# Pedal_SCH.net
KiCad netlist of a schematic drawn in Altium Designer
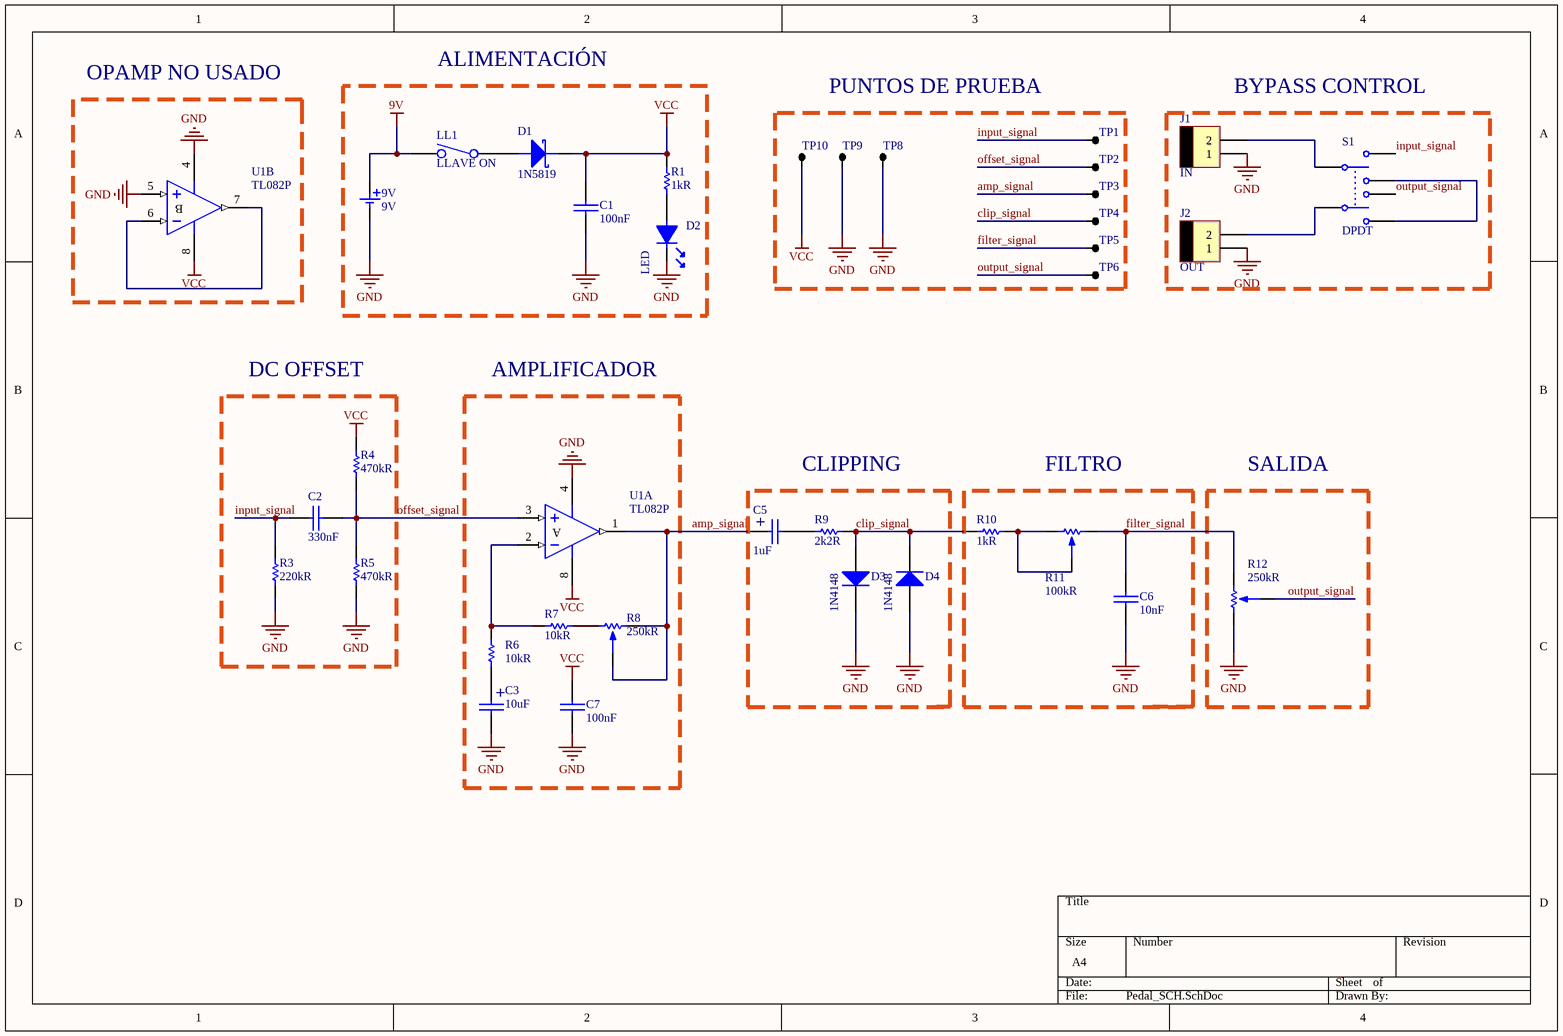
[diagram p0: Pedal_SCH.SchDoc]

(export (version "E")
  (design (tool "Eeschema 10.0.6"))
  (components
    (comp (ref "9V")
      (value "9V")
      (footprint "MOLEX2")
      (description "BATERIA")
      (libsource (lib "LIBEBAL") (part "BATERIA"))
    )
    (comp (ref "C1") (value "100nF") (footprint "0805") (libsource (lib "LIBEBAL") (part "CAP")))
    (comp (ref "C2") (value "330nF") (footprint "CAP_FILM") (libsource (lib "LIBEBAL") (part "CAP")))
    (comp (ref "C3") (value "10uF") (footprint "CAP100RP") (libsource (lib "LIBEBAL") (part "CAPPOL")))
    (comp (ref "C5") (value "1uF") (footprint "CAP100RP") (libsource (lib "LIBEBAL") (part "CAPPOL")))
    (comp (ref "C6") (value "10nF") (footprint "CAP_FILM_POLY") (libsource (lib "LIBEBAL") (part "CAP")))
    (comp (ref "C7") (value "100nF") (footprint "0805") (libsource (lib "LIBEBAL") (part "CAP")))
    (comp (ref "D1") (value "1N5819") (footprint "DO-41") (libsource (lib "LIB2013") (part "DIODE SCHOTTKY")))
    (comp (ref "D2") (value "LED") (footprint "MOLEX2") (libsource (lib "LIBEBAL") (part "LED")))
    (comp (ref "D3")
      (value "1N4148")
      (footprint "DO-35")
      (description "High Conductance Fast Diode")
      (libsource (lib "Miscellaneous Devices") (part "Diode 1N4148"))
    )
    (comp (ref "D4")
      (value "1N4148")
      (footprint "DO-35")
      (description "High Conductance Fast Diode")
      (libsource (lib "Miscellaneous Devices") (part "Diode 1N4148"))
    )
    (comp (ref "J1")
      (value "IN")
      (footprint "MOLEX2")
      (description "INPUT")
      (libsource (lib "LIBEBAL") (part "MOLEX2"))
    )
    (comp (ref "J2") (value "OUT") (footprint "MOLEX2") (libsource (lib "LIBEBAL") (part "MOLEX2")))
    (comp (ref "LL1")
      (value "LLAVE ON")
      (footprint "MOLEX2")
      (description "Llave ON")
      (libsource (lib "LIB2013") (part "LLAVE ON"))
    )
    (comp (ref "R1") (value "1kR") (footprint "0805") (libsource (lib "LIBEBAL") (part "RES")))
    (comp (ref "R3") (value "220kR") (footprint "0805") (libsource (lib "LIBEBAL") (part "RES")))
    (comp (ref "R4") (value "470kR") (footprint "0805") (libsource (lib "LIBEBAL") (part "RES")))
    (comp (ref "R5") (value "470kR") (footprint "0805") (libsource (lib "LIBEBAL") (part "RES")))
    (comp (ref "R6") (value "10kR") (footprint "0805") (libsource (lib "LIBEBAL") (part "RES")))
    (comp (ref "R7") (value "10kR") (footprint "0805") (libsource (lib "LIBEBAL") (part "RES")))
    (comp (ref "R8") (value "250kR") (footprint "MOLEX3") (libsource (lib "") (part "POTENCIOMETRO_1")))
    (comp (ref "R9") (value "2k2R") (footprint "0805") (libsource (lib "LIBEBAL") (part "RES")))
    (comp (ref "R10") (value "1kR") (footprint "0805") (libsource (lib "LIBEBAL") (part "RES")))
    (comp (ref "R11") (value "100kR") (footprint "MOLEX3") (libsource (lib "") (part "POTENCIOMETRO_1")))
    (comp (ref "R12") (value "250kR") (footprint "MOLEX3") (libsource (lib "LIBEBAL") (part "POTENCIOMETRO")))
    (comp (ref "S1")
      (value "DPDT")
      (footprint "MOLEX6")
      (description "Double-Pole, Double-Throw Switch")
      (fields (field (name "PUBLISHER") "Altium Limited"))
      (libsource (lib "Miscellaneous Devices") (part "SW-DPDT"))
    )
    (comp (ref "TP1") (value "IN") (footprint "TPTH") (libsource (lib "LIBEBAL") (part "TP")))
    (comp (ref "TP2") (value "OFF") (footprint "TPTH") (libsource (lib "LIBEBAL") (part "TP")))
    (comp (ref "TP3") (value "AMP") (footprint "TPTH") (libsource (lib "LIBEBAL") (part "TP")))
    (comp (ref "TP4") (value "CLI") (footprint "TPTH") (libsource (lib "LIBEBAL") (part "TP")))
    (comp (ref "TP5") (value "FIL") (footprint "TPTH") (libsource (lib "LIBEBAL") (part "TP")))
    (comp (ref "TP6") (value "OUT") (footprint "TPTH") (libsource (lib "LIBEBAL") (part "TP")))
    (comp (ref "TP8") (value "GND") (footprint "TPTH") (libsource (lib "LIBEBAL") (part "TP")))
    (comp (ref "TP9") (value "GND") (footprint "TPTH") (libsource (lib "LIBEBAL") (part "TP")))
    (comp (ref "TP10") (value "VCC") (footprint "TPTH") (libsource (lib "LIBEBAL") (part "TP")))
    (comp (ref "U1")
      (value "TL082P")
      (footprint "Pedal_PCB:P008")
      (description "JFET-Input Operational Amplifier")
      (fields (field (name "PUBLISHER") "Altium Limited"))
      (libsource (lib "Pedal_SCH") (part "TL082P"))
    )
  )
  (nets
    (net (code "1") (name "/amp_signal") (class "Default")
      (node (ref "C5") (pin "1") (pinfunction "1_1") (pintype "passive"))
      (node (ref "R8") (pin "1") (pinfunction "1_1") (pintype "passive"))
      (node (ref "R8") (pin "2") (pinfunction "2_2") (pintype "passive"))
      (node (ref "TP3") (pin "1") (pinfunction "1_1") (pintype "passive"))
      (node (ref "U1") (pin "1") (pinfunction "OUT_1") (pintype "output"))
    )
    (net (code "2") (name "/clip_signal") (class "Default")
      (node (ref "D3") (pin "1") (pinfunction "A_1") (pintype "passive"))
      (node (ref "D4") (pin "2") (pinfunction "K_2") (pintype "passive"))
      (node (ref "R10") (pin "2") (pinfunction "2_2") (pintype "passive"))
      (node (ref "R9") (pin "2") (pinfunction "2_2") (pintype "passive"))
      (node (ref "TP4") (pin "1") (pinfunction "1_1") (pintype "passive"))
    )
    (net (code "3") (name "/filter_signal") (class "Default")
      (node (ref "C6") (pin "1") (pinfunction "1_1") (pintype "passive"))
      (node (ref "R11") (pin "1") (pinfunction "1_1") (pintype "passive"))
      (node (ref "R12") (pin "1") (pinfunction "1_1") (pintype "passive"))
      (node (ref "TP5") (pin "1") (pinfunction "1_1") (pintype "passive"))
    )
    (net (code "4") (name "/input_signal") (class "Default")
      (node (ref "C2") (pin "1") (pinfunction "1_1") (pintype "passive"))
      (node (ref "R3") (pin "1") (pinfunction "1_1") (pintype "passive"))
      (node (ref "S1") (pin "5") (pinfunction "5_5") (pintype "passive"))
      (node (ref "TP1") (pin "1") (pinfunction "1_1") (pintype "passive"))
    )
    (net (code "5") (name "/offset_signal") (class "Default")
      (node (ref "C2") (pin "2") (pinfunction "2_2") (pintype "passive"))
      (node (ref "R4") (pin "1") (pinfunction "1_1") (pintype "passive"))
      (node (ref "R5") (pin "1") (pinfunction "1_1") (pintype "passive"))
      (node (ref "TP2") (pin "1") (pinfunction "1_1") (pintype "passive"))
      (node (ref "U1") (pin "3") (pinfunction "IN+_3") (pintype "input"))
    )
    (net (code "6") (name "/output_signal") (class "Default")
      (node (ref "R12") (pin "3") (pinfunction "3_3") (pintype "passive"))
      (node (ref "S1") (pin "2") (pinfunction "2_2") (pintype "passive"))
      (node (ref "TP6") (pin "1") (pinfunction "1_1") (pintype "passive"))
    )
    (net (code "7") (name "9V") (class "Default")
      (node (ref "9V") (pin "1") (pintype "passive"))
      (node (ref "LL1") (pin "2") (pinfunction "2_2") (pintype "passive"))
    )
    (net (code "8") (name "GND") (class "Default")
      (node (ref "9V") (pin "2") (pintype "passive"))
      (node (ref "C1") (pin "2") (pinfunction "2_2") (pintype "passive"))
      (node (ref "C3") (pin "2") (pinfunction "2_2") (pintype "passive"))
      (node (ref "C6") (pin "2") (pinfunction "2_2") (pintype "passive"))
      (node (ref "C7") (pin "1") (pinfunction "1_1") (pintype "passive"))
      (node (ref "D2") (pin "2") (pinfunction "2_2") (pintype "passive"))
      (node (ref "D3") (pin "2") (pinfunction "K_2") (pintype "passive"))
      (node (ref "D4") (pin "1") (pinfunction "A_1") (pintype "passive"))
      (node (ref "J1") (pin "1") (pinfunction "1_1") (pintype "passive"))
      (node (ref "J2") (pin "1") (pinfunction "1_1") (pintype "passive"))
      (node (ref "R12") (pin "2") (pinfunction "2_2") (pintype "passive"))
      (node (ref "R3") (pin "2") (pinfunction "2_2") (pintype "passive"))
      (node (ref "R5") (pin "2") (pinfunction "2_2") (pintype "passive"))
      (node (ref "TP8") (pin "1") (pinfunction "1_1") (pintype "passive"))
      (node (ref "TP9") (pin "1") (pinfunction "1_1") (pintype "passive"))
      (node (ref "U1") (pin "4") (pinfunction "V-_4") (pintype "power_in"))
      (node (ref "U1") (pin "5") (pinfunction "IN+_5") (pintype "input"))
    )
    (net (code "9") (name "Net-(C3-Pad1)") (class "Default")
      (node (ref "C3") (pin "1") (pinfunction "1_1") (pintype "passive"))
      (node (ref "R6") (pin "2") (pinfunction "2_2") (pintype "passive"))
    )
    (net (code "10") (name "Net-(C5-Pad2)") (class "Default")
      (node (ref "C5") (pin "2") (pinfunction "2_2") (pintype "passive"))
      (node (ref "R9") (pin "1") (pinfunction "1_1") (pintype "passive"))
    )
    (net (code "11") (name "Net-(D1-PadA)") (class "Default")
      (node (ref "D1") (pin "A") (pinfunction "A_A") (pintype "passive"))
      (node (ref "LL1") (pin "1") (pinfunction "1_1") (pintype "passive"))
    )
    (net (code "12") (name "Net-(D2-Pad1)") (class "Default")
      (node (ref "D2") (pin "1") (pinfunction "1_1") (pintype "passive"))
      (node (ref "R1") (pin "2") (pinfunction "2_2") (pintype "passive"))
    )
    (net (code "13") (name "Net-(J1-Pad2)") (class "Default")
      (node (ref "J1") (pin "2") (pinfunction "2_2") (pintype "passive"))
      (node (ref "S1") (pin "6") (pinfunction "6_6") (pintype "passive"))
    )
    (net (code "14") (name "Net-(J2-Pad2)") (class "Default")
      (node (ref "J2") (pin "2") (pinfunction "2_2") (pintype "passive"))
      (node (ref "S1") (pin "1") (pinfunction "1_1") (pintype "passive"))
    )
    (net (code "15") (name "Net-(R7-Pad1)") (class "Default")
      (node (ref "R7") (pin "1") (pinfunction "1_1") (pintype "passive"))
      (node (ref "R8") (pin "3") (pinfunction "3_3") (pintype "passive"))
    )
    (net (code "16") (name "Net-(R10-Pad1)") (class "Default")
      (node (ref "R10") (pin "1") (pinfunction "1_1") (pintype "passive"))
      (node (ref "R11") (pin "2") (pinfunction "2_2") (pintype "passive"))
      (node (ref "R11") (pin "3") (pinfunction "3_3") (pintype "passive"))
    )
    (net (code "17") (name "Net-(S1-Pad3)") (class "Default")
      (node (ref "S1") (pin "3") (pinfunction "3_3") (pintype "passive"))
      (node (ref "S1") (pin "4") (pinfunction "4_4") (pintype "passive"))
    )
    (net (code "18") (name "Net-(U1A-IN-)") (class "Default")
      (node (ref "R6") (pin "1") (pinfunction "1_1") (pintype "passive"))
      (node (ref "R7") (pin "2") (pinfunction "2_2") (pintype "passive"))
      (node (ref "U1") (pin "2") (pinfunction "IN-_2") (pintype "input"))
    )
    (net (code "19") (name "Net-(U1B-IN-)") (class "Default")
      (node (ref "U1") (pin "6") (pinfunction "IN-_6") (pintype "input"))
      (node (ref "U1") (pin "7") (pinfunction "OUT_7") (pintype "output"))
    )
    (net (code "20") (name "VCC") (class "Default")
      (node (ref "C1") (pin "1") (pinfunction "1_1") (pintype "passive"))
      (node (ref "C7") (pin "2") (pinfunction "2_2") (pintype "passive"))
      (node (ref "D1") (pin "K") (pinfunction "K_K") (pintype "passive"))
      (node (ref "R1") (pin "1") (pinfunction "1_1") (pintype "passive"))
      (node (ref "R4") (pin "2") (pinfunction "2_2") (pintype "passive"))
      (node (ref "TP10") (pin "1") (pinfunction "1_1") (pintype "passive"))
      (node (ref "U1") (pin "8") (pinfunction "V+_8") (pintype "power_in"))
    )
  )
)
